# EG.net
KiCad netlist of a schematic drawn in EAGLE
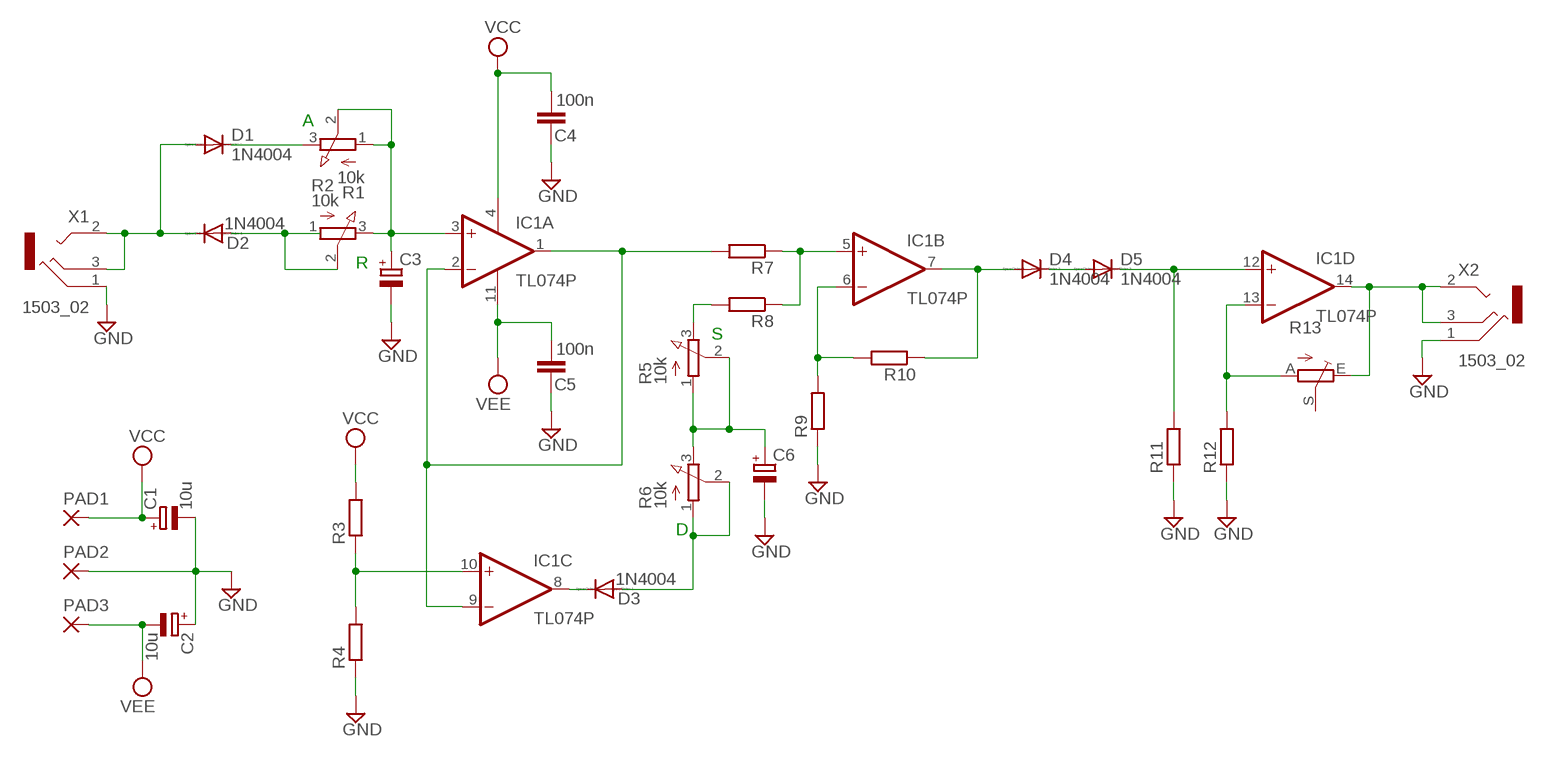
[diagram p0: schematic, sheet 1]

(export (version "E")
  (design (tool "Eeschema 10.0.6"))
  (components
    (comp (ref "C1")
      (value "10u")
      (footprint "eagle-import:E2,5-7")
      (libsource (lib "eagle-import") (part "CPOL-EUE2.5-7"))
    )
    (comp (ref "C2")
      (value "10u")
      (footprint "eagle-import:E2,5-7")
      (libsource (lib "eagle-import") (part "CPOL-EUE2.5-7"))
    )
    (comp (ref "C3")
      (value "CPOL-EUE2.5-6")
      (footprint "eagle-import:E2,5-6")
      (libsource (lib "eagle-import") (part "CPOL-EUE2.5-6"))
    )
    (comp (ref "C4")
      (value "100n")
      (footprint "eagle-import:C5B2.5")
      (libsource (lib "eagle-import") (part "C5/2.5"))
    )
    (comp (ref "C5")
      (value "100n")
      (footprint "eagle-import:C5B2.5")
      (libsource (lib "eagle-import") (part "C5/2.5"))
    )
    (comp (ref "C6")
      (value "CPOL-EUE2.5-6")
      (footprint "eagle-import:E2,5-6")
      (libsource (lib "eagle-import") (part "CPOL-EUE2.5-6"))
    )
    (comp (ref "D1")
      (value "1N4004")
      (footprint "eagle-import:DO41-10")
      (libsource (lib "eagle-import") (part "1N4004"))
    )
    (comp (ref "D2")
      (value "1N4004")
      (footprint "eagle-import:DO41-10")
      (libsource (lib "eagle-import") (part "1N4004"))
    )
    (comp (ref "D3")
      (value "1N4004")
      (footprint "eagle-import:DO41-10")
      (libsource (lib "eagle-import") (part "1N4004"))
    )
    (comp (ref "D4")
      (value "1N4004")
      (footprint "eagle-import:DO41-10")
      (libsource (lib "eagle-import") (part "1N4004"))
    )
    (comp (ref "D5")
      (value "1N4004")
      (footprint "eagle-import:DO41-10")
      (libsource (lib "eagle-import") (part "1N4004"))
    )
    (comp (ref "IC1")
      (value "TL074P")
      (footprint "eagle-import:DIL14")
      (libsource (lib "eagle-import") (part "TL074P"))
    )
    (comp (ref "PAD1")
      (value "3,17/1,1")
      (footprint "eagle-import:3,17_1,1")
      (libsource (lib "eagle-import") (part "3,17/1,1"))
    )
    (comp (ref "PAD2")
      (value "3,17/1,1")
      (footprint "eagle-import:3,17_1,1")
      (libsource (lib "eagle-import") (part "3,17/1,1"))
    )
    (comp (ref "PAD3")
      (value "3,17/1,1")
      (footprint "eagle-import:3,17_1,1")
      (libsource (lib "eagle-import") (part "3,17/1,1"))
    )
    (comp (ref "R1")
      (value "10k")
      (footprint "eagle-import:3RP_1610N")
      (libsource (lib "eagle-import") (part "3RP/1610N"))
    )
    (comp (ref "R2")
      (value "10k")
      (footprint "eagle-import:3RP_1610N")
      (libsource (lib "eagle-import") (part "3RP/1610N"))
    )
    (comp (ref "R3")
      (value "R-EU_0207/10")
      (footprint "eagle-import:0207_10")
      (libsource (lib "eagle-import") (part "R-EU_0207/10"))
    )
    (comp (ref "R4")
      (value "R-EU_0207/10")
      (footprint "eagle-import:0207_10")
      (libsource (lib "eagle-import") (part "R-EU_0207/10"))
    )
    (comp (ref "R5")
      (value "10k")
      (footprint "eagle-import:3RP_1610N")
      (libsource (lib "eagle-import") (part "3RP/1610N"))
    )
    (comp (ref "R6")
      (value "10k")
      (footprint "eagle-import:3RP_1610N")
      (libsource (lib "eagle-import") (part "3RP/1610N"))
    )
    (comp (ref "R7")
      (value "R-EU_0207/10")
      (footprint "eagle-import:0207_10")
      (libsource (lib "eagle-import") (part "R-EU_0207/10"))
    )
    (comp (ref "R8")
      (value "R-EU_0207/10")
      (footprint "eagle-import:0207_10")
      (libsource (lib "eagle-import") (part "R-EU_0207/10"))
    )
    (comp (ref "R9")
      (value "R-EU_0207/10")
      (footprint "eagle-import:0207_10")
      (libsource (lib "eagle-import") (part "R-EU_0207/10"))
    )
    (comp (ref "R10")
      (value "R-EU_0207/10")
      (footprint "eagle-import:0207_10")
      (libsource (lib "eagle-import") (part "R-EU_0207/10"))
    )
    (comp (ref "R11")
      (value "R-EU_0207/10")
      (footprint "eagle-import:0207_10")
      (libsource (lib "eagle-import") (part "R-EU_0207/10"))
    )
    (comp (ref "R12")
      (value "R-EU_0207/10")
      (footprint "eagle-import:0207_10")
      (libsource (lib "eagle-import") (part "R-EU_0207/10"))
    )
    (comp (ref "R13")
      (value "TRIM_EU-S75P")
      (footprint "eagle-import:S75P")
      (libsource (lib "eagle-import") (part "TRIM_EU-S75P"))
    )
    (comp (ref "X1")
      (value "1503_02")
      (footprint "eagle-import:1503_02")
      (libsource (lib "eagle-import") (part "1503_02"))
    )
    (comp (ref "X2")
      (value "1503_02")
      (footprint "eagle-import:1503_02")
      (libsource (lib "eagle-import") (part "1503_02"))
    )
  )
  (nets
    (net (code "1") (name "GND") (class "Default")
      (node (ref "C1") (pin "-") (pinfunction "-_-") (pintype "passive"))
      (node (ref "C2") (pin "+") (pinfunction "+_+") (pintype "passive"))
      (node (ref "C3") (pin "-") (pinfunction "-_-") (pintype "passive"))
      (node (ref "C4") (pin "1") (pinfunction "1_1") (pintype "passive"))
      (node (ref "C5") (pin "1") (pinfunction "1_1") (pintype "passive"))
      (node (ref "C6") (pin "-") (pinfunction "-_-") (pintype "passive"))
      (node (ref "PAD2") (pin "1") (pinfunction "P_1") (pintype "passive"))
      (node (ref "R11") (pin "1") (pinfunction "1_1") (pintype "passive"))
      (node (ref "R12") (pin "1") (pinfunction "1_1") (pintype "passive"))
      (node (ref "R4") (pin "1") (pinfunction "1_1") (pintype "passive"))
      (node (ref "R9") (pin "1") (pinfunction "1_1") (pintype "passive"))
      (node (ref "X1") (pin "1") (pinfunction "1_1") (pintype "passive"))
      (node (ref "X2") (pin "1") (pinfunction "1_1") (pintype "passive"))
    )
    (net (code "2") (name "Net-(D1-PadA)") (class "Default")
      (node (ref "D1") (pin "A") (pinfunction "A_A") (pintype "passive"))
      (node (ref "D2") (pin "C") (pinfunction "C_C") (pintype "passive"))
      (node (ref "X1") (pin "2") (pinfunction "2_2") (pintype "passive"))
      (node (ref "X1") (pin "3") (pinfunction "3_3") (pintype "passive"))
    )
    (net (code "3") (name "Net-(D4-PadC)") (class "Default")
      (node (ref "D4") (pin "C") (pinfunction "C_C") (pintype "passive"))
      (node (ref "D5") (pin "A") (pinfunction "A_A") (pintype "passive"))
    )
    (net (code "4") (name "Net-(IC1A-+IN)") (class "Default")
      (node (ref "C3") (pin "+") (pinfunction "+_+") (pintype "passive"))
      (node (ref "IC1") (pin "3") (pinfunction "+IN_3") (pintype "input"))
      (node (ref "R1") (pin "1") (pinfunction "A_1") (pintype "passive"))
      (node (ref "R1") (pin "2") (pinfunction "S_2") (pintype "passive"))
      (node (ref "R2") (pin "3") (pinfunction "E_3") (pintype "passive"))
    )
    (net (code "5") (name "Net-(IC1A--IN)") (class "Default")
      (node (ref "IC1") (pin "1") (pinfunction "OUT_1") (pintype "output"))
      (node (ref "IC1") (pin "2") (pinfunction "-IN_2") (pintype "input"))
      (node (ref "IC1") (pin "9") (pinfunction "-IN_9") (pintype "input"))
      (node (ref "R7") (pin "2") (pinfunction "2_2") (pintype "passive"))
    )
    (net (code "6") (name "Net-(IC1B-+IN)") (class "Default")
      (node (ref "IC1") (pin "5") (pinfunction "+IN_5") (pintype "input"))
      (node (ref "R7") (pin "1") (pinfunction "1_1") (pintype "passive"))
      (node (ref "R8") (pin "1") (pinfunction "1_1") (pintype "passive"))
    )
    (net (code "7") (name "Net-(IC1B--IN)") (class "Default")
      (node (ref "IC1") (pin "6") (pinfunction "-IN_6") (pintype "input"))
      (node (ref "R10") (pin "2") (pinfunction "2_2") (pintype "passive"))
      (node (ref "R9") (pin "2") (pinfunction "2_2") (pintype "passive"))
    )
    (net (code "8") (name "Net-(IC1B-OUT)") (class "Default")
      (node (ref "D4") (pin "A") (pinfunction "A_A") (pintype "passive"))
      (node (ref "IC1") (pin "7") (pinfunction "OUT_7") (pintype "output"))
      (node (ref "R10") (pin "1") (pinfunction "1_1") (pintype "passive"))
    )
    (net (code "9") (name "Net-(IC1C-+IN)") (class "Default")
      (node (ref "IC1") (pin "10") (pinfunction "+IN_10") (pintype "input"))
      (node (ref "R3") (pin "1") (pinfunction "1_1") (pintype "passive"))
      (node (ref "R4") (pin "2") (pinfunction "2_2") (pintype "passive"))
    )
    (net (code "10") (name "Net-(IC1C-OUT)") (class "Default")
      (node (ref "D3") (pin "C") (pinfunction "C_C") (pintype "passive"))
      (node (ref "IC1") (pin "8") (pinfunction "OUT_8") (pintype "output"))
    )
    (net (code "11") (name "Net-(IC1D-+IN)") (class "Default")
      (node (ref "D5") (pin "C") (pinfunction "C_C") (pintype "passive"))
      (node (ref "IC1") (pin "12") (pinfunction "+IN_12") (pintype "input"))
      (node (ref "R11") (pin "2") (pinfunction "2_2") (pintype "passive"))
    )
    (net (code "12") (name "Net-(IC1D--IN)") (class "Default")
      (node (ref "IC1") (pin "13") (pinfunction "-IN_13") (pintype "input"))
      (node (ref "R12") (pin "2") (pinfunction "2_2") (pintype "passive"))
      (node (ref "R13") (pin "A") (pinfunction "A_A") (pintype "passive"))
    )
    (net (code "13") (name "Net-(IC1D-OUT)") (class "Default")
      (node (ref "IC1") (pin "14") (pinfunction "OUT_14") (pintype "output"))
      (node (ref "R13") (pin "E") (pinfunction "E_E") (pintype "passive"))
      (node (ref "X2") (pin "2") (pinfunction "2_2") (pintype "passive"))
      (node (ref "X2") (pin "3") (pinfunction "3_3") (pintype "passive"))
    )
    (net (code "14") (name "Net-(R1-E)") (class "Default")
      (node (ref "D1") (pin "C") (pinfunction "C_C") (pintype "passive"))
      (node (ref "R1") (pin "3") (pinfunction "E_3") (pintype "passive"))
    )
    (net (code "15") (name "Net-(R2-A)") (class "Default")
      (node (ref "D2") (pin "A") (pinfunction "A_A") (pintype "passive"))
      (node (ref "R2") (pin "1") (pinfunction "A_1") (pintype "passive"))
      (node (ref "R2") (pin "2") (pinfunction "S_2") (pintype "passive"))
    )
    (net (code "16") (name "Net-(R5-A)") (class "Default")
      (node (ref "C6") (pin "+") (pinfunction "+_+") (pintype "passive"))
      (node (ref "R5") (pin "1") (pinfunction "A_1") (pintype "passive"))
      (node (ref "R5") (pin "2") (pinfunction "S_2") (pintype "passive"))
      (node (ref "R6") (pin "3") (pinfunction "E_3") (pintype "passive"))
    )
    (net (code "17") (name "Net-(R5-E)") (class "Default")
      (node (ref "R5") (pin "3") (pinfunction "E_3") (pintype "passive"))
      (node (ref "R8") (pin "2") (pinfunction "2_2") (pintype "passive"))
    )
    (net (code "18") (name "Net-(R6-A)") (class "Default")
      (node (ref "D3") (pin "A") (pinfunction "A_A") (pintype "passive"))
      (node (ref "R6") (pin "1") (pinfunction "A_1") (pintype "passive"))
      (node (ref "R6") (pin "2") (pinfunction "S_2") (pintype "passive"))
    )
    (net (code "19") (name "VCC") (class "Default")
      (node (ref "C1") (pin "+") (pinfunction "+_+") (pintype "passive"))
      (node (ref "C4") (pin "2") (pinfunction "2_2") (pintype "passive"))
      (node (ref "IC1") (pin "4") (pinfunction "V+_4") (pintype "power_in"))
      (node (ref "PAD1") (pin "1") (pinfunction "P_1") (pintype "passive"))
      (node (ref "R3") (pin "2") (pinfunction "2_2") (pintype "passive"))
    )
    (net (code "20") (name "VEE") (class "Default")
      (node (ref "C2") (pin "-") (pinfunction "-_-") (pintype "passive"))
      (node (ref "C5") (pin "2") (pinfunction "2_2") (pintype "passive"))
      (node (ref "IC1") (pin "11") (pinfunction "V-_11") (pintype "power_in"))
      (node (ref "PAD3") (pin "1") (pinfunction "P_1") (pintype "passive"))
    )
    (net (code "21") (name "unconnected-(R13-PadS)") (class "Default")
      (node (ref "R13") (pin "S") (pinfunction "S_S") (pintype "passive"))
    )
    (net (code "22") (name "unconnected-(X1-2-Pad2@2)") (class "Default")
      (node (ref "X1") (pin "2@2") (pinfunction "2_2@2") (pintype "passive"))
    )
    (net (code "23") (name "unconnected-(X2-2-Pad2@2)") (class "Default")
      (node (ref "X2") (pin "2@2") (pinfunction "2_2@2") (pintype "passive"))
    )
  )
)
